# MCU.net
KiCad netlist of a schematic drawn in Altium Designer
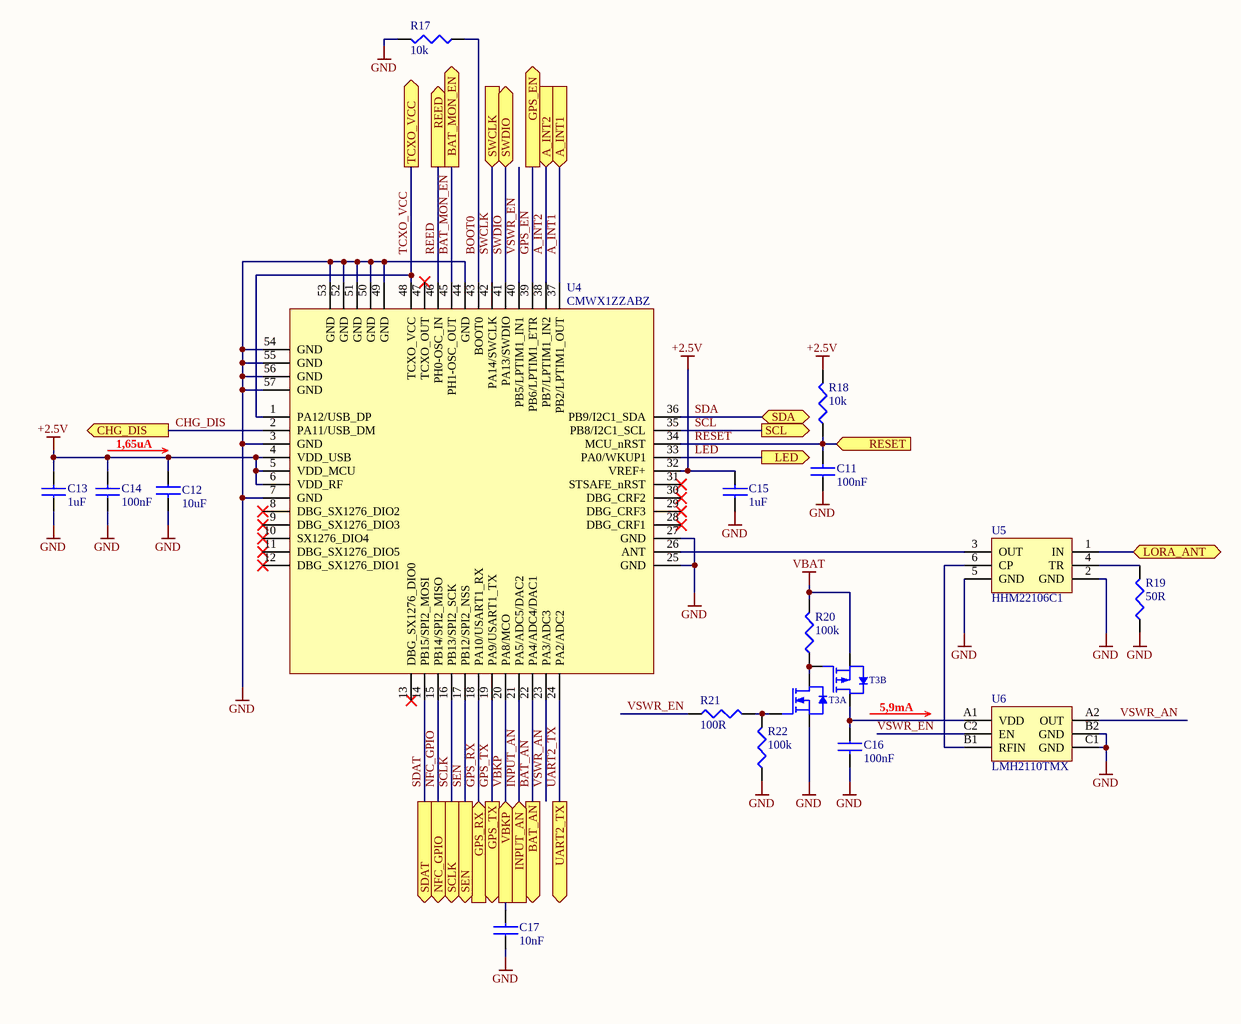
[diagram p0: MCU.SchDoc]

(export (version "E")
  (design (tool "Eeschema 10.0.6"))
  (components
    (comp (ref "C11")
      (value "100nF")
      (footprint "CAP0402")
      (description "0.1 F, 16 V,  5%, X5R, MC Series")
      (fields
        (field (name "MANUFACTURER") "Multicomp")
        (field (name "MANUFACTURER PART NUMBER") "MC0402X104J160CT")
      )
      (libsource (lib "Passive") (part "C - 100nF/0402"))
    )
    (comp (ref "C12")
      (value "10uF")
      (footprint "CAP0603")
      (description "Cap Ceramic 10uF 10V X5R 10% SMD 0603 85C Paper T/R")
      (fields
        (field (name "MANUFACTURER") "Samsung")
        (field (name "MANUFACTURER PART NUMBER") "CL10A106KP8NNNC")
      )
      (libsource (lib "Passive") (part "C - 10uF/10V"))
    )
    (comp (ref "C13")
      (value "1uF")
      (footprint "CAP0402")
      (description "CAP CER 1UF 10V 20% X5R 0402")
      (fields
        (field (name "MANUFACTURER") "Murata")
        (field (name "MANUFACTURER PART NUMBER") "GRM155R61A105ME15D")
      )
      (libsource (lib "Passive") (part "C - 1uF/0402"))
    )
    (comp (ref "C14")
      (value "100nF")
      (footprint "CAP0402")
      (description "0.1 F, 16 V,  5%, X5R, MC Series")
      (fields
        (field (name "MANUFACTURER") "Multicomp")
        (field (name "MANUFACTURER PART NUMBER") "MC0402X104J160CT")
      )
      (libsource (lib "Passive") (part "C - 100nF/0402"))
    )
    (comp (ref "C15")
      (value "1uF")
      (footprint "CAP0402")
      (description "CAP CER 1UF 10V 20% X5R 0402")
      (fields
        (field (name "MANUFACTURER") "Murata")
        (field (name "MANUFACTURER PART NUMBER") "GRM155R61A105ME15D")
      )
      (libsource (lib "Passive") (part "C - 1uF/0402"))
    )
    (comp (ref "C16")
      (value "100nF")
      (footprint "CAP0402")
      (description "0.1 F, 16 V,  5%, X5R, MC Series")
      (fields
        (field (name "MANUFACTURER") "Multicomp")
        (field (name "MANUFACTURER PART NUMBER") "MC0402X104J160CT")
      )
      (libsource (lib "Passive") (part "C - 100nF/0402"))
    )
    (comp (ref "C17")
      (value "10nF")
      (footprint "CAP0402")
      (description "CAP CER 10000PF 16V X7R 0402")
      (fields
        (field (name "MANUFACTURER") "Murata")
        (field (name "MANUFACTURER PART NUMBER") "GRM155R71C103KA01D")
      )
      (libsource (lib "Passive") (part "C - 10nF/0402"))
    )
    (comp (ref "R17")
      (value "10k")
      (footprint "RES0402")
      (description "10 kohm, 50 V, 0402 [1005 Metric], 62.5 mW,  1%, MCWR Series")
      (fields
        (field (name "MANUFACTURER") "Multicomp")
        (field (name "MANUFACTURER PART NUMBER") "MCWR04X1002FTL")
      )
      (libsource (lib "Passive") (part "R - 10k/0402"))
    )
    (comp (ref "R18")
      (value "10k")
      (footprint "RES0402")
      (description "10 kohm, 50 V, 0402 [1005 Metric], 62.5 mW,  1%, MCWR Series")
      (fields
        (field (name "MANUFACTURER") "Multicomp")
        (field (name "MANUFACTURER PART NUMBER") "MCWR04X1002FTL")
      )
      (libsource (lib "Passive") (part "R - 10k/0402"))
    )
    (comp (ref "R19")
      (value "50R")
      (footprint "RES0402")
      (description "50 ohm, FC Series, 30 V, Thin Film, 50 mW")
      (fields
        (field (name "MANUFACTURER") "Vishay")
        (field (name "MANUFACTURER PART NUMBER") "CRCW060351R0FKEA")
      )
      (libsource (lib "Passive") (part "R - 50R"))
    )
    (comp (ref "R20")
      (value "100k")
      (footprint "RES0402")
      (description "100KOHM, 1%, 0.0625W")
      (fields
        (field (name "MANUFACTURER") "Multicomp")
        (field (name "MANUFACTURER PART NUMBER") "MCWR04X1003FTL")
      )
      (libsource (lib "Passive") (part "R - 100k/0402"))
    )
    (comp (ref "R21")
      (value "100R")
      (footprint "RES0402")
      (description "100 ohm, 50 V, 0402 [1005 Metric], 62.5 mW,  1%")
      (fields
        (field (name "MANUFACTURER") "Multicomp")
        (field (name "MANUFACTURER PART NUMBER") "MCMR04X1000FTL")
      )
      (libsource (lib "Passive") (part "R - 100R/0402"))
    )
    (comp (ref "R22")
      (value "100k")
      (footprint "RES0402")
      (description "100KOHM, 1%, 0.0625W")
      (fields
        (field (name "MANUFACTURER") "Multicomp")
        (field (name "MANUFACTURER PART NUMBER") "MCWR04X1003FTL")
      )
      (libsource (lib "Passive") (part "R - 100k/0402"))
    )
    (comp (ref "T3")
      (value "VT6M1T2CR")
      (footprint "VMT6")
      (description "Dual MOSFET, N and P Channel, 100 mA, 20 V, 2.5 ohm, 4.5 V, 1 V")
      (fields (field (name "AUTHOR") "Ciril Golob"))
      (libsource (lib "Active") (part "T_M - VT6M1T2CR"))
    )
    (comp (ref "U4")
      (value "CMWX1ZZABZ")
      (footprint "Lora Module ES0")
      (description "RF Module, FSK, OOK, LoRa, 4.8Kbps, 915MHz, -135.5dBm, 2.2V to 3.6V, I2C, SPI, UART, USB")
      (fields
        (field (name "MANUFACTURER") "Murata")
        (field (name "MANUFACTURER PART NUMBER") "CMWX1ZZABZ-091")
      )
      (libsource (lib "Active") (part "MCU - CMWX1ZZABZ"))
    )
    (comp (ref "U5")
      (value "HHM22106C1")
      (footprint "HHM22106C1")
      (description "Signal Conditioning DIRECTIONAL COUPLER 700-2700MHz")
      (fields (field (name "MANUFACTURER") "u-blox") (field (name "MANUFACTURER PART NUMBER") "MAX-M8Q-0"))
      (libsource (lib "Active") (part "RF - HHM22106C1"))
    )
    (comp (ref "U6")
      (value "LMH2110TMX")
      (footprint "DSBGA-6")
      (description "RF Detector IC GSM, EDGE, CDMA 50MHz ~ 8GHz -40dBm ~ 5dBm ±0,5dB")
      (fields (field (name "MANUFACTURER") "u-blox") (field (name "MANUFACTURER PART NUMBER") "MAX-M8Q-0"))
      (libsource (lib "Active") (part "RF - LMH2110TMX"))
    )
  )
  (nets
    (net (code "1") (name "+2.5V") (class "Default")
      (node (ref "C12") (pin "1") (pinfunction "1_1") (pintype "passive"))
      (node (ref "C13") (pin "2") (pinfunction "2_2") (pintype "passive"))
      (node (ref "C14") (pin "2") (pinfunction "2_2") (pintype "passive"))
      (node (ref "C15") (pin "2") (pinfunction "2_2") (pintype "passive"))
      (node (ref "R18") (pin "2") (pinfunction "2_2") (pintype "passive"))
      (node (ref "U4") (pin "32") (pinfunction "VREF+_32") (pintype "passive"))
      (node (ref "U4") (pin "4") (pinfunction "VDD_USB_4") (pintype "passive"))
      (node (ref "U4") (pin "5") (pinfunction "VDD_MCU_5") (pintype "passive"))
      (node (ref "U4") (pin "6") (pinfunction "VDD_RF_6") (pintype "passive"))
    )
    (net (code "2") (name "/A_INT1") (class "Default")
      (node (ref "U4") (pin "37") (pinfunction "PB2/LPTIM1_OUT_37") (pintype "passive"))
    )
    (net (code "3") (name "/A_INT2") (class "Default")
      (node (ref "U4") (pin "38") (pinfunction "PB7/LPTIM1_IN2_38") (pintype "passive"))
    )
    (net (code "4") (name "/BAT_AN") (class "Default")
      (node (ref "U4") (pin "22") (pinfunction "PA4/ADC4/DAC1_22") (pintype "passive"))
    )
    (net (code "5") (name "/BAT_MON_EN") (class "Default")
      (node (ref "U4") (pin "45") (pinfunction "PH1-OSC_OUT_45") (pintype "passive"))
    )
    (net (code "6") (name "/BOOT0") (class "Default")
      (node (ref "R17") (pin "1") (pinfunction "1_1") (pintype "passive"))
      (node (ref "U4") (pin "43") (pinfunction "BOOT0_43") (pintype "passive"))
    )
    (net (code "7") (name "/CHG_DIS") (class "Default")
      (node (ref "U4") (pin "2") (pinfunction "PA11/USB_DM_2") (pintype "passive"))
    )
    (net (code "8") (name "/GPS_EN") (class "Default")
      (node (ref "U4") (pin "39") (pinfunction "PB6/LPTIM1_ETR_39") (pintype "passive"))
    )
    (net (code "9") (name "/GPS_RX") (class "Default")
      (node (ref "U4") (pin "18") (pinfunction "PA10/USART1_RX_18") (pintype "passive"))
    )
    (net (code "10") (name "/GPS_TX") (class "Default")
      (node (ref "U4") (pin "19") (pinfunction "PA9/USART1_TX_19") (pintype "passive"))
    )
    (net (code "11") (name "/INPUT_AN") (class "Default")
      (node (ref "U4") (pin "21") (pinfunction "PA5/ADC5/DAC2_21") (pintype "passive"))
    )
    (net (code "12") (name "/LED") (class "Default")
      (node (ref "U4") (pin "33") (pinfunction "PA0/WKUP1_33") (pintype "passive"))
    )
    (net (code "13") (name "/LORA_ANT") (class "Default")
      (node (ref "U5") (pin "1") (pinfunction "IN_1") (pintype "passive"))
    )
    (net (code "14") (name "/NFC_GPIO") (class "Default")
      (node (ref "U4") (pin "15") (pinfunction "PB14/SPI2_MISO_15") (pintype "passive"))
    )
    (net (code "15") (name "/REED") (class "Default")
      (node (ref "U4") (pin "46") (pinfunction "PH0-OSC_IN_46") (pintype "passive"))
    )
    (net (code "16") (name "/RESET") (class "Default")
      (node (ref "C11") (pin "2") (pinfunction "2_2") (pintype "passive"))
      (node (ref "R18") (pin "1") (pinfunction "1_1") (pintype "passive"))
      (node (ref "U4") (pin "34") (pinfunction "MCU_nRST_34") (pintype "passive"))
    )
    (net (code "17") (name "/SCL") (class "Default")
      (node (ref "U4") (pin "35") (pinfunction "PB8/I2C1_SCL_35") (pintype "passive"))
    )
    (net (code "18") (name "/SCLK") (class "Default")
      (node (ref "U4") (pin "16") (pinfunction "PB13/SPI2_SCK_16") (pintype "passive"))
    )
    (net (code "19") (name "/SDA") (class "Default")
      (node (ref "U4") (pin "36") (pinfunction "PB9/I2C1_SDA_36") (pintype "passive"))
    )
    (net (code "20") (name "/SDAT") (class "Default")
      (node (ref "U4") (pin "14") (pinfunction "PB15/SPI2_MOSI_14") (pintype "passive"))
    )
    (net (code "21") (name "/SEN") (class "Default")
      (node (ref "U4") (pin "17") (pinfunction "PB12/SPI2_NSS_17") (pintype "passive"))
    )
    (net (code "22") (name "/SWCLK") (class "Default")
      (node (ref "U4") (pin "42") (pinfunction "PA14/SWCLK_42") (pintype "passive"))
    )
    (net (code "23") (name "/SWDIO") (class "Default")
      (node (ref "U4") (pin "41") (pinfunction "PA13/SWDIO_41") (pintype "passive"))
    )
    (net (code "24") (name "/TCXO_VCC") (class "Default")
      (node (ref "U4") (pin "1") (pinfunction "PA12/USB_DP_1") (pintype "passive"))
      (node (ref "U4") (pin "48") (pinfunction "TCXO_VCC_48") (pintype "passive"))
    )
    (net (code "25") (name "/UART2_TX") (class "Default")
      (node (ref "U4") (pin "24") (pinfunction "PA2/ADC2_24") (pintype "passive"))
    )
    (net (code "26") (name "/VBKP") (class "Default")
      (node (ref "C17") (pin "2") (pinfunction "2_2") (pintype "passive"))
      (node (ref "U4") (pin "20") (pinfunction "PA8/MCO_20") (pintype "passive"))
    )
    (net (code "27") (name "/VSWR_AN") (class "Default")
      (node (ref "U4") (pin "23") (pinfunction "PA3/ADC3_23") (pintype "passive"))
      (node (ref "U6") (pin "A2") (pinfunction "OUT_A2") (pintype "passive"))
    )
    (net (code "28") (name "/VSWR_EN") (class "Default")
      (node (ref "R21") (pin "1") (pinfunction "1_1") (pintype "passive"))
      (node (ref "U4") (pin "40") (pinfunction "PB5/LPTIM1_IN1_40") (pintype "passive"))
      (node (ref "U6") (pin "C2") (pinfunction "EN_C2") (pintype "passive"))
    )
    (net (code "29") (name "GND") (class "Default")
      (node (ref "C11") (pin "1") (pinfunction "1_1") (pintype "passive"))
      (node (ref "C12") (pin "2") (pinfunction "2_2") (pintype "passive"))
      (node (ref "C13") (pin "1") (pinfunction "1_1") (pintype "passive"))
      (node (ref "C14") (pin "1") (pinfunction "1_1") (pintype "passive"))
      (node (ref "C15") (pin "1") (pinfunction "1_1") (pintype "passive"))
      (node (ref "C16") (pin "2") (pinfunction "2_2") (pintype "passive"))
      (node (ref "C17") (pin "1") (pinfunction "1_1") (pintype "passive"))
      (node (ref "R17") (pin "2") (pinfunction "2_2") (pintype "passive"))
      (node (ref "R19") (pin "1") (pinfunction "1_1") (pintype "passive"))
      (node (ref "R22") (pin "1") (pinfunction "1_1") (pintype "passive"))
      (node (ref "T3") (pin "1") (pinfunction "S1_1") (pintype "passive"))
      (node (ref "U4") (pin "25") (pinfunction "GND_25") (pintype "passive"))
      (node (ref "U4") (pin "27") (pinfunction "GND_27") (pintype "passive"))
      (node (ref "U4") (pin "3") (pinfunction "GND_3") (pintype "passive"))
      (node (ref "U4") (pin "44") (pinfunction "GND_44") (pintype "passive"))
      (node (ref "U4") (pin "49") (pinfunction "GND_49") (pintype "passive"))
      (node (ref "U4") (pin "50") (pinfunction "GND_50") (pintype "passive"))
      (node (ref "U4") (pin "51") (pinfunction "GND_51") (pintype "passive"))
      (node (ref "U4") (pin "52") (pinfunction "GND_52") (pintype "passive"))
      (node (ref "U4") (pin "53") (pinfunction "GND_53") (pintype "passive"))
      (node (ref "U4") (pin "54") (pinfunction "GND_54") (pintype "passive"))
      (node (ref "U4") (pin "55") (pinfunction "GND_55") (pintype "passive"))
      (node (ref "U4") (pin "56") (pinfunction "GND_56") (pintype "passive"))
      (node (ref "U4") (pin "57") (pinfunction "GND_57") (pintype "passive"))
      (node (ref "U4") (pin "7") (pinfunction "GND_7") (pintype "passive"))
      (node (ref "U5") (pin "2") (pinfunction "GND_2") (pintype "passive"))
      (node (ref "U5") (pin "5") (pinfunction "GND_5") (pintype "passive"))
      (node (ref "U6") (pin "B2") (pinfunction "GND_B2") (pintype "passive"))
      (node (ref "U6") (pin "C1") (pinfunction "GND_C1") (pintype "passive"))
    )
    (net (code "30") (name "Net-(T3A-D1)") (class "Default")
      (node (ref "R20") (pin "1") (pinfunction "1_1") (pintype "passive"))
      (node (ref "T3") (pin "5") (pinfunction "G2_5") (pintype "passive"))
      (node (ref "T3") (pin "6") (pinfunction "D1_6") (pintype "passive"))
    )
    (net (code "31") (name "Net-(T3A-G1)") (class "Default")
      (node (ref "R21") (pin "2") (pinfunction "2_2") (pintype "passive"))
      (node (ref "R22") (pin "2") (pinfunction "2_2") (pintype "passive"))
      (node (ref "T3") (pin "2") (pinfunction "G1_2") (pintype "passive"))
    )
    (net (code "32") (name "Net-(T3B-D2)") (class "Default")
      (node (ref "C16") (pin "1") (pinfunction "1_1") (pintype "passive"))
      (node (ref "T3") (pin "3") (pinfunction "D2_3") (pintype "passive"))
      (node (ref "U6") (pin "A1") (pinfunction "VDD_A1") (pintype "passive"))
    )
    (net (code "33") (name "Net-(U4-ANT)") (class "Default")
      (node (ref "U4") (pin "26") (pinfunction "ANT_26") (pintype "passive"))
      (node (ref "U5") (pin "3") (pinfunction "OUT_3") (pintype "passive"))
    )
    (net (code "34") (name "Net-(U5-CP)") (class "Default")
      (node (ref "U5") (pin "6") (pinfunction "CP_6") (pintype "passive"))
      (node (ref "U6") (pin "B1") (pinfunction "RFIN_B1") (pintype "passive"))
    )
    (net (code "35") (name "Net-(U5-TR)") (class "Default")
      (node (ref "R19") (pin "2") (pinfunction "2_2") (pintype "passive"))
      (node (ref "U5") (pin "4") (pinfunction "TR_4") (pintype "passive"))
    )
    (net (code "36") (name "VBAT") (class "Default")
      (node (ref "R20") (pin "2") (pinfunction "2_2") (pintype "passive"))
      (node (ref "T3") (pin "4") (pinfunction "S2_4") (pintype "passive"))
    )
    (net (code "37") (name "unconnected-(U4-DBG_CRF1-Pad28)") (class "Default")
      (node (ref "U4") (pin "28") (pinfunction "DBG_CRF1_28") (pintype "passive+no_connect"))
    )
    (net (code "38") (name "unconnected-(U4-DBG_CRF2-Pad30)") (class "Default")
      (node (ref "U4") (pin "30") (pinfunction "DBG_CRF2_30") (pintype "passive+no_connect"))
    )
    (net (code "39") (name "unconnected-(U4-DBG_CRF3-Pad29)") (class "Default")
      (node (ref "U4") (pin "29") (pinfunction "DBG_CRF3_29") (pintype "passive+no_connect"))
    )
    (net (code "40") (name "unconnected-(U4-DBG_SX1276_DIO0-Pad13)") (class "Default")
      (node (ref "U4") (pin "13") (pinfunction "DBG_SX1276_DIO0_13") (pintype "passive+no_connect"))
    )
    (net (code "41") (name "unconnected-(U4-DBG_SX1276_DIO1-Pad12)") (class "Default")
      (node (ref "U4") (pin "12") (pinfunction "DBG_SX1276_DIO1_12") (pintype "passive+no_connect"))
    )
    (net (code "42") (name "unconnected-(U4-DBG_SX1276_DIO2-Pad8)") (class "Default")
      (node (ref "U4") (pin "8") (pinfunction "DBG_SX1276_DIO2_8") (pintype "passive+no_connect"))
    )
    (net (code "43") (name "unconnected-(U4-DBG_SX1276_DIO3-Pad9)") (class "Default")
      (node (ref "U4") (pin "9") (pinfunction "DBG_SX1276_DIO3_9") (pintype "passive+no_connect"))
    )
    (net (code "44") (name "unconnected-(U4-DBG_SX1276_DIO5-Pad11)") (class "Default")
      (node (ref "U4") (pin "11") (pinfunction "DBG_SX1276_DIO5_11") (pintype "passive+no_connect"))
    )
    (net (code "45") (name "unconnected-(U4-STSAFE_nRST-Pad31)") (class "Default")
      (node (ref "U4") (pin "31") (pinfunction "STSAFE_nRST_31") (pintype "passive+no_connect"))
    )
    (net (code "46") (name "unconnected-(U4-SX1276_DIO4-Pad10)") (class "Default")
      (node (ref "U4") (pin "10") (pinfunction "SX1276_DIO4_10") (pintype "passive+no_connect"))
    )
    (net (code "47") (name "unconnected-(U4-TCXO_OUT-Pad47)") (class "Default")
      (node (ref "U4") (pin "47") (pinfunction "TCXO_OUT_47") (pintype "passive+no_connect"))
    )
  )
)
